# 3V3-CAN-Unisolated.net
KiCad netlist of a schematic drawn in Altium Designer
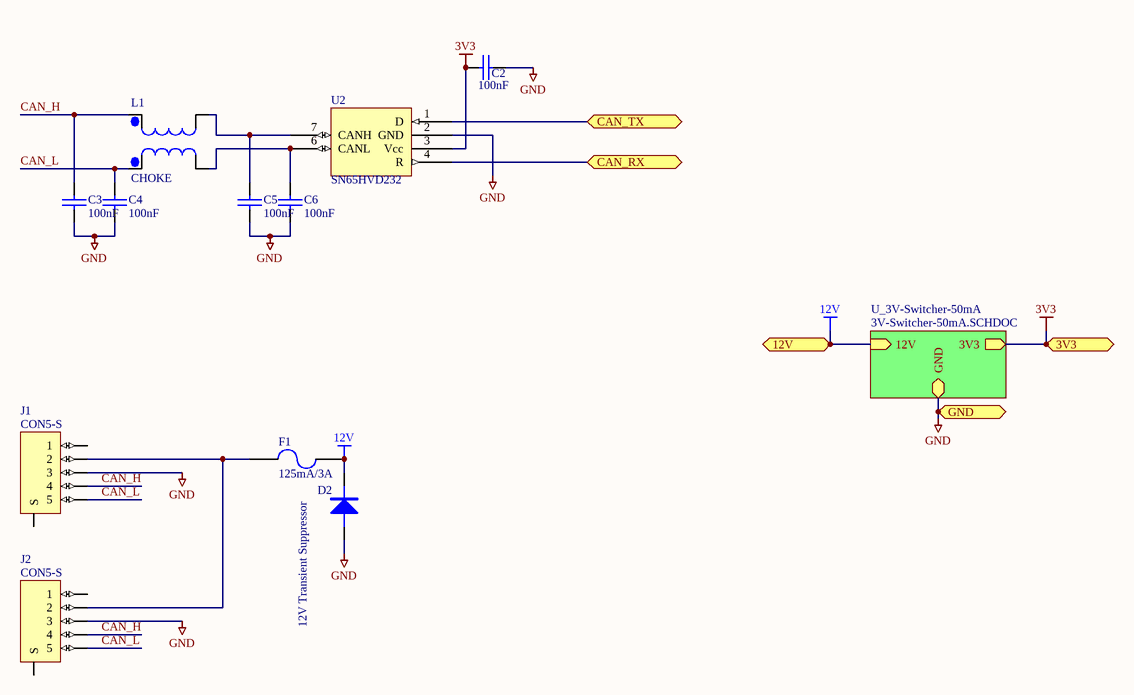
[diagram p0: 3V3-CAN-Unisolated.SchDoc]

(export (version "E")
  (design (tool "Eeschema 10.0.6"))
  (components
    (comp (ref "C2")
      (value "100nF")
      (footprint "0603")
      (description "Capacitor")
      (libsource (lib "*") (part "CAP"))
    )
    (comp (ref "C3")
      (value "100nF")
      (footprint "0603")
      (description "Capacitor")
      (libsource (lib "*") (part "CAP"))
    )
    (comp (ref "C4")
      (value "100nF")
      (footprint "0603")
      (description "Capacitor")
      (libsource (lib "*") (part "CAP"))
    )
    (comp (ref "C5")
      (value "100nF")
      (footprint "0603")
      (description "Capacitor")
      (libsource (lib "*") (part "CAP"))
    )
    (comp (ref "C6")
      (value "100nF")
      (footprint "0603")
      (description "Capacitor")
      (libsource (lib "*") (part "CAP"))
    )
    (comp (ref "D2")
      (value "12V Transient Suppressor")
      (footprint "SMA")
      (description "Diode")
      (libsource (lib "RCLDQ") (part "DIODE"))
    )
    (comp (ref "F1")
      (value "125mA/3A")
      (footprint "LITTELFUSE-154")
      (description "Fuse")
      (libsource (lib "*") (part "FUSE2"))
    )
    (comp (ref "J1")
      (value "CON5-S")
      (footprint "TRIAD5F")
      (description "Connector, 2 pin, with shield @ S")
      (libsource (lib "*") (part "CON5-S"))
    )
    (comp (ref "J2")
      (value "CON5-S")
      (footprint "TRIAD5F")
      (description "Connector, 2 pin, with shield @ S")
      (libsource (lib "*") (part "CON5-S"))
    )
    (comp (ref "L1") (value "CHOKE") (footprint "Epcos-Choke") (libsource (lib "RCLDQ") (part "CHOKE")))
    (comp (ref "U2")
      (value "SN65HVD232")
      (footprint "SO8")
      (description "3.3V CAN Transciever")
      (libsource (lib "*") (part "SN65HVD232"))
    )
  )
  (nets
    (net (code "1") (name "/CAN_H") (class "Default")
      (node (ref "C3") (pin "2") (pinfunction "2_2") (pintype "passive"))
      (node (ref "J1") (pin "4") (pinfunction "4_4") (pintype "bidirectional"))
      (node (ref "J2") (pin "4") (pinfunction "4_4") (pintype "bidirectional"))
      (node (ref "L1") (pin "1") (pinfunction "1_1") (pintype "passive"))
    )
    (net (code "2") (name "/CAN_L") (class "Default")
      (node (ref "C4") (pin "1") (pinfunction "1_1") (pintype "passive"))
      (node (ref "J1") (pin "5") (pinfunction "5_5") (pintype "bidirectional"))
      (node (ref "J2") (pin "5") (pinfunction "5_5") (pintype "bidirectional"))
      (node (ref "L1") (pin "2") (pinfunction "2_2") (pintype "passive"))
    )
    (net (code "3") (name "/CAN_RX") (class "Default")
      (node (ref "U2") (pin "4") (pinfunction "R_4") (pintype "output"))
    )
    (net (code "4") (name "/CAN_TX") (class "Default")
      (node (ref "U2") (pin "1") (pinfunction "D_1") (pintype "input"))
    )
    (net (code "5") (name "3V3") (class "Default")
      (node (ref "C2") (pin "2") (pinfunction "2_2") (pintype "passive"))
      (node (ref "U2") (pin "3") (pinfunction "Vcc_3") (pintype "power_in"))
    )
    (net (code "6") (name "12V") (class "Default")
      (node (ref "D2") (pin "K") (pinfunction "K_K") (pintype "passive"))
      (node (ref "F1") (pin "2") (pinfunction "2_2") (pintype "passive"))
    )
    (net (code "7") (name "GND") (class "Default")
      (node (ref "C2") (pin "1") (pinfunction "1_1") (pintype "passive"))
      (node (ref "C3") (pin "1") (pinfunction "1_1") (pintype "passive"))
      (node (ref "C4") (pin "2") (pinfunction "2_2") (pintype "passive"))
      (node (ref "C5") (pin "2") (pinfunction "2_2") (pintype "passive"))
      (node (ref "C6") (pin "2") (pinfunction "2_2") (pintype "passive"))
      (node (ref "D2") (pin "A") (pinfunction "A_A") (pintype "passive"))
      (node (ref "J1") (pin "3") (pinfunction "3_3") (pintype "bidirectional"))
      (node (ref "J2") (pin "3") (pinfunction "3_3") (pintype "bidirectional"))
      (node (ref "U2") (pin "2") (pinfunction "GND_2") (pintype "power_in"))
    )
    (net (code "8") (name "Net-(F1-Pad1)") (class "Default")
      (node (ref "F1") (pin "1") (pinfunction "1_1") (pintype "passive"))
      (node (ref "J1") (pin "2") (pinfunction "2_2") (pintype "bidirectional"))
      (node (ref "J2") (pin "2") (pinfunction "2_2") (pintype "bidirectional"))
    )
    (net (code "9") (name "Net-(U2-CANH)") (class "Default")
      (node (ref "C5") (pin "1") (pinfunction "1_1") (pintype "passive"))
      (node (ref "L1") (pin "4") (pinfunction "4_4") (pintype "passive"))
      (node (ref "U2") (pin "7") (pinfunction "CANH_7") (pintype "bidirectional"))
    )
    (net (code "10") (name "Net-(U2-CANL)") (class "Default")
      (node (ref "C6") (pin "1") (pinfunction "1_1") (pintype "passive"))
      (node (ref "L1") (pin "3") (pinfunction "3_3") (pintype "passive"))
      (node (ref "U2") (pin "6") (pinfunction "CANL_6") (pintype "bidirectional"))
    )
    (net (code "11") (name "unconnected-(J1-Pad1)") (class "Default")
      (node (ref "J1") (pin "1") (pinfunction "1_1") (pintype "bidirectional"))
    )
    (net (code "12") (name "unconnected-(J1-S-Pad0)") (class "Default")
      (node (ref "J1") (pin "0") (pinfunction "S_0") (pintype "bidirectional"))
    )
    (net (code "13") (name "unconnected-(J2-Pad1)") (class "Default")
      (node (ref "J2") (pin "1") (pinfunction "1_1") (pintype "bidirectional"))
    )
    (net (code "14") (name "unconnected-(J2-S-Pad0)") (class "Default")
      (node (ref "J2") (pin "0") (pinfunction "S_0") (pintype "bidirectional"))
    )
  )
)
